# RADIOMASTER.net
KiCad netlist of a schematic drawn in Altium Designer
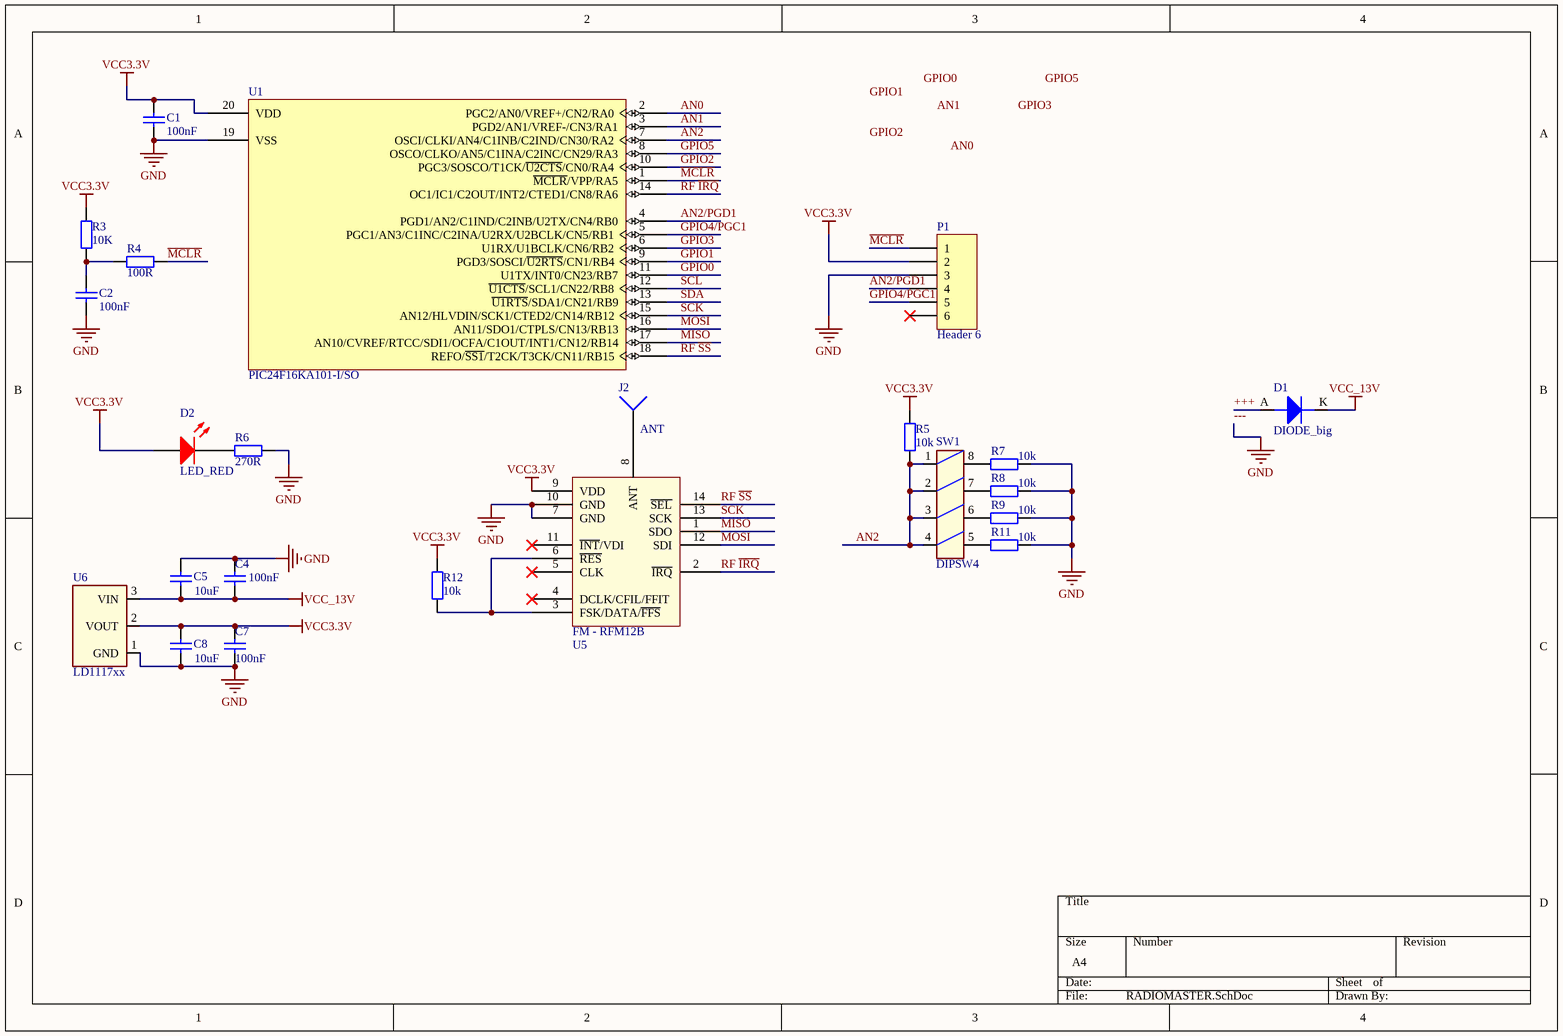
[diagram p0: RADIOMASTER.SchDoc]

(export (version "E")
  (design (tool "Eeschema 10.0.6"))
  (components
    (comp (ref "C1")
      (value "100nF")
      (footprint "FP_0805_CAP_060")
      (description "Capacitor")
      (fields (field (name "PUBLISHER") "Altium Limited"))
      (libsource (lib "Miscellaneous Devices") (part "Cap"))
    )
    (comp (ref "C2")
      (value "100nF")
      (footprint "FP_0805_CAP_060")
      (description "Capacitor")
      (fields (field (name "PUBLISHER") "Altium Limited"))
      (libsource (lib "Miscellaneous Devices") (part "Cap"))
    )
    (comp (ref "C4")
      (value "100nF")
      (footprint "FP_0603_CAP_080")
      (description "Capacitor")
      (fields (field (name "PUBLISHER") "Altium Limited"))
      (libsource (lib "Miscellaneous Devices") (part "Cap"))
    )
    (comp (ref "C5")
      (value "10uF")
      (footprint "FP_1206_CAP_085")
      (description "Capacitor")
      (fields (field (name "PUBLISHER") "Altium Limited"))
      (libsource (lib "Miscellaneous Devices") (part "Cap"))
    )
    (comp (ref "C7")
      (value "100nF")
      (footprint "FP_0603_CAP_080")
      (description "Capacitor")
      (fields (field (name "PUBLISHER") "Altium Limited"))
      (libsource (lib "Miscellaneous Devices") (part "Cap"))
    )
    (comp (ref "C8")
      (value "10uF")
      (footprint "FP_1206_CAP_085")
      (description "Capacitor")
      (fields (field (name "PUBLISHER") "Altium Limited"))
      (libsource (lib "Miscellaneous Devices") (part "Cap"))
    )
    (comp (ref "D1")
      (value "DIODE_big")
      (footprint "FP_SMA DO214AC")
      (libsource (lib "Diode") (part "DIODE_big"))
    )
    (comp (ref "D2")
      (value "LED_RED")
      (footprint "FP_0805_LED_RED")
      (description "Typical LED")
      (libsource (lib "Led_optical") (part "LED_R"))
    )
    (comp (ref "J2")
      (value "ANT")
      (footprint "PIN1")
      (description "Socket")
      (fields (field (name "PUBLISHER") "Altium Limited"))
      (libsource (lib "Miscellaneous Connectors") (part "Socket"))
    )
    (comp (ref "P1")
      (value "Header 6")
      (footprint "HDR1X6")
      (description "Header, 6-Pin")
      (fields (field (name "PUBLISHER") "Altium Limited"))
      (libsource (lib "Miscellaneous Connectors") (part "Header 6"))
    )
    (comp (ref "R3")
      (value "10K")
      (footprint "FP_0805_RES")
      (description "Resistor")
      (fields (field (name "PUBLISHER") "Altium Limited"))
      (libsource (lib "Miscellaneous Devices") (part "Res3"))
    )
    (comp (ref "R4")
      (value "100R")
      (footprint "FP_0805_RES")
      (description "Resistor")
      (fields (field (name "PUBLISHER") "Altium Limited"))
      (libsource (lib "") (part "Res3_1"))
    )
    (comp (ref "R5")
      (value "10k")
      (footprint "FP_0805_RES")
      (description "Resistor")
      (fields (field (name "PUBLISHER") "Altium Limited"))
      (libsource (lib "Miscellaneous Devices") (part "Res3"))
    )
    (comp (ref "R6")
      (value "270R")
      (footprint "FP_0805_RES")
      (description "Resistor")
      (fields (field (name "PUBLISHER") "Altium Limited"))
      (libsource (lib "") (part "Res3_1"))
    )
    (comp (ref "R7")
      (value "10k")
      (footprint "FP_0805_RES")
      (description "Resistor")
      (fields (field (name "PUBLISHER") "Altium Limited"))
      (libsource (lib "") (part "Res3_1"))
    )
    (comp (ref "R8")
      (value "10k")
      (footprint "FP_0805_RES")
      (description "Resistor")
      (fields (field (name "PUBLISHER") "Altium Limited"))
      (libsource (lib "") (part "Res3_1"))
    )
    (comp (ref "R9")
      (value "10k")
      (footprint "FP_0805_RES")
      (description "Resistor")
      (fields (field (name "PUBLISHER") "Altium Limited"))
      (libsource (lib "") (part "Res3_1"))
    )
    (comp (ref "R11")
      (value "10k")
      (footprint "FP_0805_RES")
      (description "Resistor")
      (fields (field (name "PUBLISHER") "Altium Limited"))
      (libsource (lib "") (part "Res3_1"))
    )
    (comp (ref "R12")
      (value "10k")
      (footprint "FP_0805_RES")
      (description "Resistor")
      (fields (field (name "PUBLISHER") "Altium Limited"))
      (libsource (lib "") (part "Res3_2"))
    )
    (comp (ref "SW1")
      (value "DIPSW4")
      (footprint "DIP switch 4 TH")
      (libsource (lib "Switch") (part "DIPSW4"))
    )
    (comp (ref "U1")
      (value "PIC24F16KA101-I/SO")
      (footprint "SOIC-SO20_N")
      (fields (field (name "PUBLISHER") "Altium Limited"))
      (libsource (lib "Microchip Microcontroller 16-Bit PIC24F") (part "PIC24F16KA101-I/SO"))
    )
    (comp (ref "U5")
      (value "RFM12B")
      (footprint "RFM12B-S1")
      (description "FM Module")
      (libsource (lib "EtherIOv2") (part "RFM12B"))
    )
    (comp (ref "U6")
      (value "LD1117xx")
      (footprint "SUPPLY_SOT223")
      (description "LD1117xx 3,3V lin reg")
      (libsource (lib "Supply") (part "LD1117xx"))
    )
  )
  (nets
    (net (code "1") (name "/+++") (class "Default")
      (node (ref "D1") (pin "A") (pinfunction "A_A") (pintype "passive"))
    )
    (net (code "2") (name "/AN0") (class "Default")
      (node (ref "U1") (pin "2") (pinfunction "PGC2/AN0/VREF+/CN2/RA0_2") (pintype "bidirectional"))
    )
    (net (code "3") (name "/AN1") (class "Default")
      (node (ref "U1") (pin "3") (pinfunction "PGD2/AN1/VREF-/CN3/RA1_3") (pintype "bidirectional"))
    )
    (net (code "4") (name "/AN2") (class "Default")
      (node (ref "R5") (pin "2") (pinfunction "2_2") (pintype "passive"))
      (node (ref "SW1") (pin "1") (pinfunction "1_1") (pintype "passive"))
      (node (ref "SW1") (pin "2") (pinfunction "2_2") (pintype "passive"))
      (node (ref "SW1") (pin "3") (pinfunction "3_3") (pintype "passive"))
      (node (ref "SW1") (pin "4") (pinfunction "4_4") (pintype "passive"))
      (node (ref "U1") (pin "7") (pinfunction "OSCI/CLKI/AN4/C1INB/C2IND/CN30/RA2_7") (pintype "bidirectional"))
    )
    (net (code "5") (name "/AN2{slash}PGD1") (class "Default")
      (node (ref "P1") (pin "4") (pinfunction "4_4") (pintype "passive"))
      (node (ref "U1") (pin "4") (pinfunction "PGD1/AN2/C1IND/C2INB/U2TX/CN4/RB0_4") (pintype "bidirectional"))
    )
    (net (code "6") (name "/GPIO0") (class "Default")
      (node (ref "U1") (pin "11") (pinfunction "U1TX/INT0/CN23/RB7_11") (pintype "bidirectional"))
    )
    (net (code "7") (name "/GPIO1") (class "Default")
      (node (ref "U1") (pin "9") (pinfunction "PGD3/SOSCI/~{U2RTS}/CN1/RB4_9") (pintype "bidirectional"))
    )
    (net (code "8") (name "/GPIO2") (class "Default")
      (node (ref "U1") (pin "10") (pinfunction "PGC3/SOSCO/T1CK/~{U2CTS}/CN0/RA4_10") (pintype "bidirectional"))
    )
    (net (code "9") (name "/GPIO3") (class "Default")
      (node (ref "U1") (pin "6") (pinfunction "U1RX/U1BCLK/CN6/RB2_6") (pintype "bidirectional"))
    )
    (net (code "10") (name "/GPIO4{slash}PGC1") (class "Default")
      (node (ref "P1") (pin "5") (pinfunction "5_5") (pintype "passive"))
      (node (ref "U1") (pin "5") (pinfunction "PGC1/AN3/C1INC/C2INA/U2RX/U2BCLK/CN5/RB1_5") (pintype "bidirectional"))
    )
    (net (code "11") (name "/GPIO5") (class "Default")
      (node (ref "U1") (pin "8") (pinfunction "OSCO/CLKO/AN5/C1INA/C2INC/CN29/RA3_8") (pintype "bidirectional"))
    )
    (net (code "12") (name "/MISO") (class "Default")
      (node (ref "U1") (pin "17") (pinfunction "AN10/CVREF/RTCC/SDI1/OCFA/C1OUT/INT1/CN12/RB14_17") (pintype "bidirectional"))
      (node (ref "U5") (pin "1") (pinfunction "SDO_1") (pintype "passive"))
    )
    (net (code "13") (name "/MOSI") (class "Default")
      (node (ref "U1") (pin "16") (pinfunction "AN11/SDO1/CTPLS/CN13/RB13_16") (pintype "bidirectional"))
      (node (ref "U5") (pin "12") (pinfunction "SDI_12") (pintype "passive"))
    )
    (net (code "14") (name "/RF ~{IRQ}") (class "Default")
      (node (ref "U1") (pin "14") (pinfunction "OC1/IC1/C2OUT/INT2/CTED1/CN8/RA6_14") (pintype "bidirectional"))
      (node (ref "U5") (pin "2") (pinfunction "~{IRQ}_2") (pintype "passive"))
    )
    (net (code "15") (name "/RF ~{SS}") (class "Default")
      (node (ref "U1") (pin "18") (pinfunction "REFO/~{SS1}/T2CK/T3CK/CN11/RB15_18") (pintype "bidirectional"))
      (node (ref "U5") (pin "14") (pinfunction "~{SEL}_14") (pintype "passive"))
    )
    (net (code "16") (name "/SCK") (class "Default")
      (node (ref "U1") (pin "15") (pinfunction "AN12/HLVDIN/SCK1/CTED2/CN14/RB12_15") (pintype "bidirectional"))
      (node (ref "U5") (pin "13") (pinfunction "SCK_13") (pintype "passive"))
    )
    (net (code "17") (name "/SCL") (class "Default")
      (node (ref "U1") (pin "12") (pinfunction "~{U1CTS}/SCL1/CN22/RB8_12") (pintype "bidirectional"))
    )
    (net (code "18") (name "/SDA") (class "Default")
      (node (ref "U1") (pin "13") (pinfunction "~{U1RTS}/SDA1/CN21/RB9_13") (pintype "bidirectional"))
    )
    (net (code "19") (name "/~{MCLR}") (class "Default")
      (node (ref "P1") (pin "1") (pinfunction "1_1") (pintype "passive"))
      (node (ref "R4") (pin "1") (pinfunction "1_1") (pintype "passive"))
      (node (ref "U1") (pin "1") (pinfunction "~{MCLR}/VPP/RA5_1") (pintype "bidirectional"))
    )
    (net (code "20") (name "GND") (class "Default")
      (node (ref "C1") (pin "1") (pinfunction "1_1") (pintype "passive"))
      (node (ref "C2") (pin "1") (pinfunction "1_1") (pintype "passive"))
      (node (ref "C4") (pin "1") (pinfunction "1_1") (pintype "passive"))
      (node (ref "C5") (pin "2") (pinfunction "2_2") (pintype "passive"))
      (node (ref "C7") (pin "2") (pinfunction "2_2") (pintype "passive"))
      (node (ref "C8") (pin "1") (pinfunction "1_1") (pintype "passive"))
      (node (ref "P1") (pin "3") (pinfunction "3_3") (pintype "passive"))
      (node (ref "R11") (pin "1") (pinfunction "1_1") (pintype "passive"))
      (node (ref "R6") (pin "1") (pinfunction "1_1") (pintype "passive"))
      (node (ref "R7") (pin "1") (pinfunction "1_1") (pintype "passive"))
      (node (ref "R8") (pin "1") (pinfunction "1_1") (pintype "passive"))
      (node (ref "R9") (pin "1") (pinfunction "1_1") (pintype "passive"))
      (node (ref "U1") (pin "19") (pinfunction "VSS_19") (pintype "power_in"))
      (node (ref "U5") (pin "10") (pinfunction "GND_10") (pintype "passive"))
      (node (ref "U5") (pin "7") (pinfunction "GND_7") (pintype "passive"))
      (node (ref "U6") (pin "1") (pinfunction "GND_1") (pintype "passive"))
    )
    (net (code "21") (name "Net-(C2-Pad2)") (class "Default")
      (node (ref "C2") (pin "2") (pinfunction "2_2") (pintype "passive"))
      (node (ref "R3") (pin "2") (pinfunction "2_2") (pintype "passive"))
      (node (ref "R4") (pin "2") (pinfunction "2_2") (pintype "passive"))
    )
    (net (code "22") (name "Net-(D2-PadK)") (class "Default")
      (node (ref "D2") (pin "K") (pinfunction "K_K") (pintype "passive"))
      (node (ref "R6") (pin "2") (pinfunction "2_2") (pintype "passive"))
    )
    (net (code "23") (name "Net-(R7-Pad2)") (class "Default")
      (node (ref "R7") (pin "2") (pinfunction "2_2") (pintype "passive"))
      (node (ref "SW1") (pin "8") (pinfunction "8_8") (pintype "passive"))
    )
    (net (code "24") (name "Net-(R8-Pad2)") (class "Default")
      (node (ref "R8") (pin "2") (pinfunction "2_2") (pintype "passive"))
      (node (ref "SW1") (pin "7") (pinfunction "7_7") (pintype "passive"))
    )
    (net (code "25") (name "Net-(R9-Pad2)") (class "Default")
      (node (ref "R9") (pin "2") (pinfunction "2_2") (pintype "passive"))
      (node (ref "SW1") (pin "6") (pinfunction "6_6") (pintype "passive"))
    )
    (net (code "26") (name "Net-(R11-Pad2)") (class "Default")
      (node (ref "R11") (pin "2") (pinfunction "2_2") (pintype "passive"))
      (node (ref "SW1") (pin "5") (pinfunction "5_5") (pintype "passive"))
    )
    (net (code "27") (name "Net-(U5-ANT)") (class "Default")
      (node (ref "J2") (pin "1") (pinfunction "1_1") (pintype "passive"))
      (node (ref "U5") (pin "8") (pinfunction "ANT_8") (pintype "passive"))
    )
    (net (code "28") (name "Net-(U5-FSK{slash}DATA{slash}~{FFS})") (class "Default")
      (node (ref "R12") (pin "1") (pinfunction "1_1") (pintype "passive"))
      (node (ref "U5") (pin "3") (pinfunction "FSK/DATA/~{FFS}_3") (pintype "passive"))
      (node (ref "U5") (pin "6") (pinfunction "~{RES}_6") (pintype "passive"))
    )
    (net (code "29") (name "VCC3.3V") (class "Default")
      (node (ref "C1") (pin "2") (pinfunction "2_2") (pintype "passive"))
      (node (ref "C7") (pin "1") (pinfunction "1_1") (pintype "passive"))
      (node (ref "C8") (pin "2") (pinfunction "2_2") (pintype "passive"))
      (node (ref "D2") (pin "A") (pinfunction "A_A") (pintype "passive"))
      (node (ref "P1") (pin "2") (pinfunction "2_2") (pintype "passive"))
      (node (ref "R12") (pin "2") (pinfunction "2_2") (pintype "passive"))
      (node (ref "R3") (pin "1") (pinfunction "1_1") (pintype "passive"))
      (node (ref "R5") (pin "1") (pinfunction "1_1") (pintype "passive"))
      (node (ref "U1") (pin "20") (pinfunction "VDD_20") (pintype "power_in"))
      (node (ref "U5") (pin "9") (pinfunction "VDD_9") (pintype "passive"))
      (node (ref "U6") (pin "2") (pinfunction "VOUT_2") (pintype "passive"))
    )
    (net (code "30") (name "VCC_13V") (class "Default")
      (node (ref "C4") (pin "2") (pinfunction "2_2") (pintype "passive"))
      (node (ref "C5") (pin "1") (pinfunction "1_1") (pintype "passive"))
      (node (ref "D1") (pin "K") (pinfunction "K_K") (pintype "passive"))
      (node (ref "U6") (pin "3") (pinfunction "VIN_3") (pintype "passive"))
    )
    (net (code "31") (name "unconnected-(P1-Pad6)") (class "Default")
      (node (ref "P1") (pin "6") (pinfunction "6_6") (pintype "passive+no_connect"))
    )
    (net (code "32") (name "unconnected-(U5-CLK-Pad5)") (class "Default")
      (node (ref "U5") (pin "5") (pinfunction "CLK_5") (pintype "passive+no_connect"))
    )
    (net (code "33") (name "unconnected-(U5-DCLK{slash}CFIL{slash}FFIT-Pad4)") (class "Default")
      (node (ref "U5") (pin "4") (pinfunction "DCLK/CFIL/FFIT_4") (pintype "passive+no_connect"))
    )
    (net (code "34") (name "unconnected-(U5-~{INT}{slash}VDI-Pad11)") (class "Default")
      (node (ref "U5") (pin "11") (pinfunction "~{INT}/VDI_11") (pintype "passive+no_connect"))
    )
  )
)
